# Power.net
KiCad netlist of a schematic drawn in Altium Designer
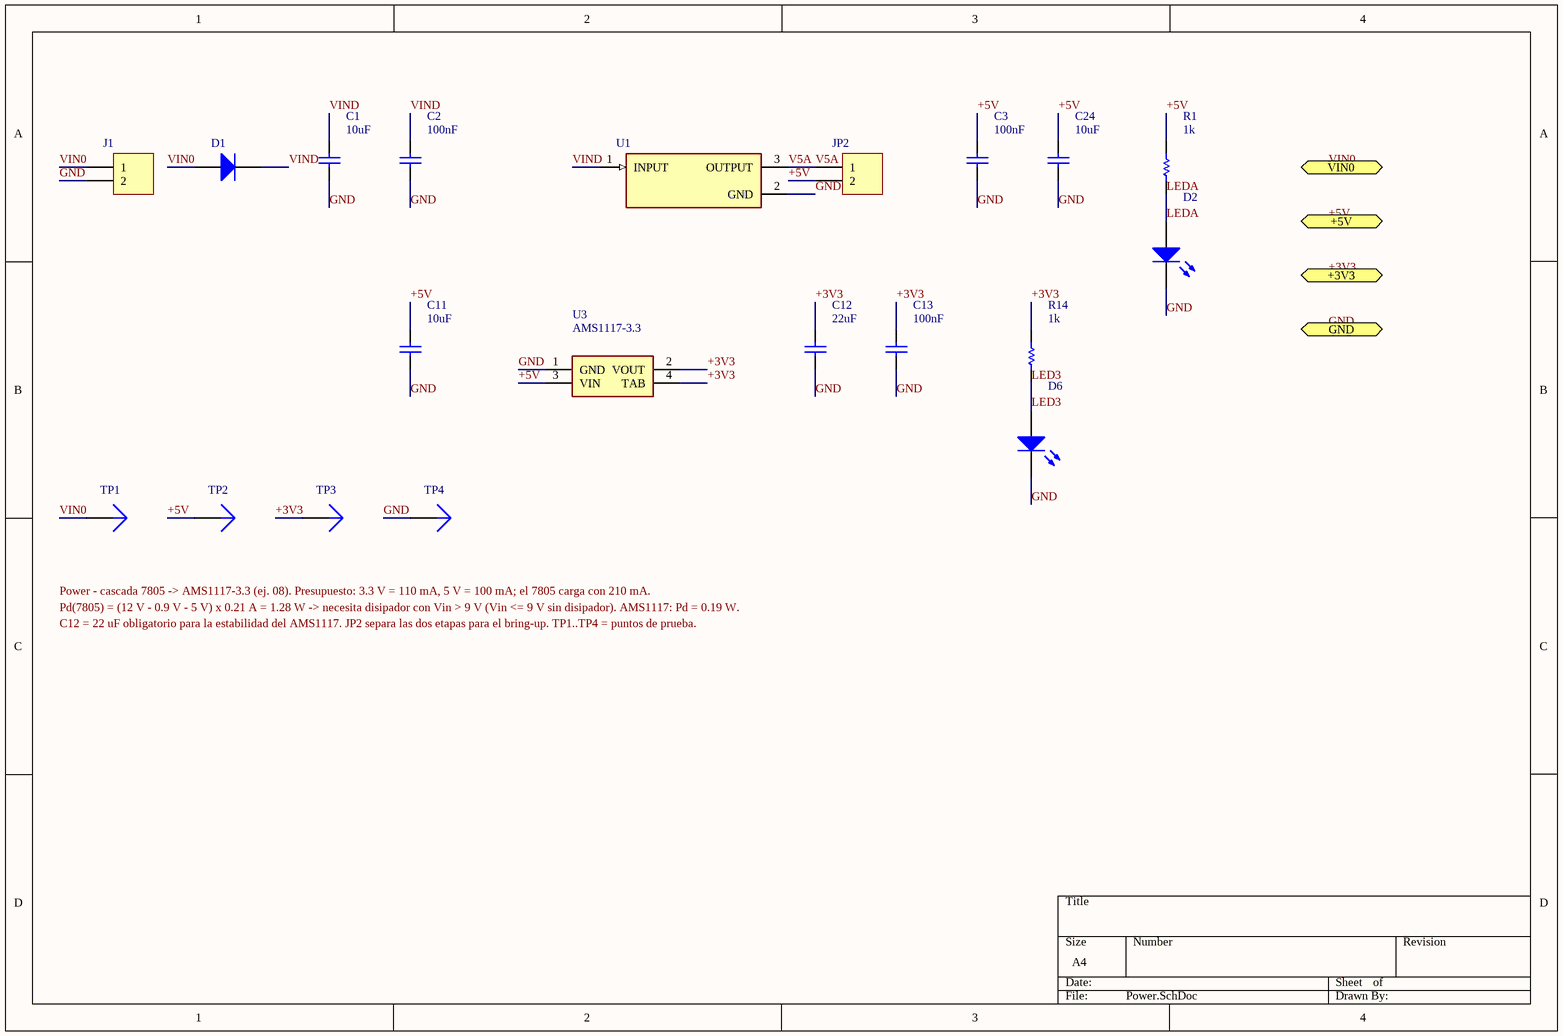
[diagram p0: Power.SchDoc]

(export (version "E")
  (design (tool "Eeschema 10.0.6"))
  (components
    (comp (ref "C1")
      (value "10uF")
      (description "Capacitor 10uF")
      (fields
        (field (name "MANUFACTURER") "KEMET")
        (field (name "MANUFACTURER PART NUMBER") "C0805C10610uF")
        (field (name "PUBLISHER") "Altium Limited")
      )
      (libsource (lib "Miscellaneous Devices") (part "Cap"))
    )
    (comp (ref "C2")
      (value "100nF")
      (description "Capacitor 100nF")
      (fields
        (field (name "MANUFACTURER") "KEMET")
        (field (name "MANUFACTURER PART NUMBER") "C0603C100nF")
        (field (name "PUBLISHER") "Altium Limited")
      )
      (libsource (lib "Miscellaneous Devices") (part "Cap"))
    )
    (comp (ref "C3")
      (value "100nF")
      (description "Capacitor 100nF")
      (fields
        (field (name "MANUFACTURER") "KEMET")
        (field (name "MANUFACTURER PART NUMBER") "C0603C100nF")
        (field (name "PUBLISHER") "Altium Limited")
      )
      (libsource (lib "Miscellaneous Devices") (part "Cap"))
    )
    (comp (ref "C11")
      (value "10uF")
      (description "Capacitor 10uF")
      (fields
        (field (name "MANUFACTURER") "KEMET")
        (field (name "MANUFACTURER PART NUMBER") "C0805C10610uF")
        (field (name "PUBLISHER") "Altium Limited")
      )
      (libsource (lib "Miscellaneous Devices") (part "Cap"))
    )
    (comp (ref "C12")
      (value "22uF")
      (description "Capacitor 22uF")
      (fields
        (field (name "MANUFACTURER") "KEMET")
        (field (name "MANUFACTURER PART NUMBER") "C1206C22622uF")
        (field (name "PUBLISHER") "Altium Limited")
      )
      (libsource (lib "Miscellaneous Devices") (part "Cap"))
    )
    (comp (ref "C13")
      (value "100nF")
      (description "Capacitor 100nF")
      (fields
        (field (name "MANUFACTURER") "KEMET")
        (field (name "MANUFACTURER PART NUMBER") "C0603C100nF")
        (field (name "PUBLISHER") "Altium Limited")
      )
      (libsource (lib "Miscellaneous Devices") (part "Cap"))
    )
    (comp (ref "C24")
      (value "10uF")
      (description "Capacitor 10uF")
      (fields
        (field (name "MANUFACTURER") "KEMET")
        (field (name "MANUFACTURER PART NUMBER") "C0805C10610uF")
        (field (name "PUBLISHER") "Altium Limited")
      )
      (libsource (lib "Miscellaneous Devices") (part "Cap"))
    )
    (comp (ref "D1")
      (value "Diode 1N4007")
      (description "Proteccion de polaridad inversa")
      (fields
        (field (name "MANUFACTURER") "Diodes Inc.")
        (field (name "MANUFACTURER PART NUMBER") "1N4007")
        (field (name "PUBLISHER") "Altium Limited")
      )
      (libsource (lib "Miscellaneous Devices") (part "Diode 1N4007"))
    )
    (comp (ref "D2")
      (value "LED1")
      (description "LED de alimentacion (5 V)")
      (fields
        (field (name "MANUFACTURER") "Kingbright")
        (field (name "MANUFACTURER PART NUMBER") "WP7113ID")
        (field (name "PUBLISHER") "Altium Limited")
      )
      (libsource (lib "Miscellaneous Devices") (part "LED1"))
    )
    (comp (ref "D6")
      (value "LED1")
      (description "LED de alimentacion (3.3 V)")
      (fields
        (field (name "MANUFACTURER") "Kingbright")
        (field (name "MANUFACTURER PART NUMBER") "WP7113GD")
        (field (name "PUBLISHER") "Altium Limited")
      )
      (libsource (lib "Miscellaneous Devices") (part "LED1"))
    )
    (comp (ref "J1")
      (value "Header 2")
      (description "Entrada 9-12 V DC: pin1 VIN, pin2 GND")
      (fields
        (field (name "MANUFACTURER") "Generic")
        (field (name "MANUFACTURER PART NUMBER") "Pin header 1x2 / borne")
        (field (name "PUBLISHER") "Altium Limited")
      )
      (libsource (lib "Miscellaneous Connectors") (part "Header 2"))
    )
    (comp (ref "JP2")
      (value "Header 2")
      (description "Jumper de separacion entre etapas")
      (fields
        (field (name "MANUFACTURER") "Generic")
        (field (name "MANUFACTURER PART NUMBER") "Pin header 1x2")
        (field (name "PUBLISHER") "Altium Limited")
      )
      (libsource (lib "Miscellaneous Connectors") (part "Header 2"))
    )
    (comp (ref "R1")
      (value "1k")
      (description "Resistor 1k 0603")
      (fields
        (field (name "MANUFACTURER") "Yageo")
        (field (name "MANUFACTURER PART NUMBER") "RC0603FR-071K")
        (field (name "PUBLISHER") "Altium Limited")
      )
      (libsource (lib "Miscellaneous Devices") (part "Res1"))
    )
    (comp (ref "R14")
      (value "1k")
      (description "Resistor 1k 0603")
      (fields
        (field (name "MANUFACTURER") "Yageo")
        (field (name "MANUFACTURER PART NUMBER") "RC0603FR-071K")
        (field (name "PUBLISHER") "Altium Limited")
      )
      (libsource (lib "Miscellaneous Devices") (part "Res1"))
    )
    (comp (ref "TP1")
      (value "Plug")
      (description "Punto de prueba VIN0")
      (fields
        (field (name "MANUFACTURER") "Generic")
        (field (name "MANUFACTURER PART NUMBER") "Test point")
        (field (name "PUBLISHER") "Altium Limited")
      )
      (libsource (lib "Miscellaneous Connectors") (part "Plug"))
    )
    (comp (ref "TP2")
      (value "Plug")
      (description "Punto de prueba +5V")
      (fields
        (field (name "MANUFACTURER") "Generic")
        (field (name "MANUFACTURER PART NUMBER") "Test point")
        (field (name "PUBLISHER") "Altium Limited")
      )
      (libsource (lib "Miscellaneous Connectors") (part "Plug"))
    )
    (comp (ref "TP3")
      (value "Plug")
      (description "Punto de prueba +3V3")
      (fields
        (field (name "MANUFACTURER") "Generic")
        (field (name "MANUFACTURER PART NUMBER") "Test point")
        (field (name "PUBLISHER") "Altium Limited")
      )
      (libsource (lib "Miscellaneous Connectors") (part "Plug"))
    )
    (comp (ref "TP4")
      (value "Plug")
      (description "Punto de prueba GND")
      (fields
        (field (name "MANUFACTURER") "Generic")
        (field (name "MANUFACTURER PART NUMBER") "Test point")
        (field (name "PUBLISHER") "Altium Limited")
      )
      (libsource (lib "Miscellaneous Connectors") (part "Plug"))
    )
    (comp (ref "U1")
      (value "LM7805T")
      (footprint "TO254P1011X457X1950-3")
      (description "Regulador 5 V, 1.5 A, TO-220 (necesita disipador si Vin>9 V)")
      (fields (field (name "MF") "TAEJIN") (field (name "MANUFACTURER") "STMicroelectronics"))
      (libsource (lib "LM7805T") (part "LM7805T"))
    )
    (comp (ref "U3")
      (value "AMS1117-3.3")
      (footprint "SOT223_N")
      (description "LDO 3.3 V 1 A SOT-223")
      (fields (field (name "MANUFACTURER") "Advanced Monolithic Systems"))
      (libsource (lib "*") (part "AMS1117-3.3"))
    )
  )
  (nets
    (net (code "1") (name "/+3V3") (class "Default")
      (node (ref "C12") (pin "2") (pinfunction "2_2") (pintype "passive"))
      (node (ref "C13") (pin "2") (pinfunction "2_2") (pintype "passive"))
      (node (ref "R14") (pin "2") (pinfunction "2_2") (pintype "passive"))
      (node (ref "TP3") (pin "1") (pinfunction "1_1") (pintype "passive"))
      (node (ref "U3") (pin "2") (pinfunction "VOUT_2") (pintype "power_in"))
      (node (ref "U3") (pin "4") (pinfunction "TAB_4") (pintype "power_in"))
    )
    (net (code "2") (name "/+5V") (class "Default")
      (node (ref "C11") (pin "2") (pinfunction "2_2") (pintype "passive"))
      (node (ref "C24") (pin "2") (pinfunction "2_2") (pintype "passive"))
      (node (ref "C3") (pin "2") (pinfunction "2_2") (pintype "passive"))
      (node (ref "JP2") (pin "2") (pinfunction "2_2") (pintype "passive"))
      (node (ref "R1") (pin "2") (pinfunction "2_2") (pintype "passive"))
      (node (ref "TP2") (pin "1") (pinfunction "1_1") (pintype "passive"))
      (node (ref "U3") (pin "3") (pinfunction "VIN_3") (pintype "power_in"))
    )
    (net (code "3") (name "/GND") (class "Default")
      (node (ref "C1") (pin "1") (pinfunction "1_1") (pintype "passive"))
      (node (ref "C11") (pin "1") (pinfunction "1_1") (pintype "passive"))
      (node (ref "C12") (pin "1") (pinfunction "1_1") (pintype "passive"))
      (node (ref "C13") (pin "1") (pinfunction "1_1") (pintype "passive"))
      (node (ref "C2") (pin "1") (pinfunction "1_1") (pintype "passive"))
      (node (ref "C24") (pin "1") (pinfunction "1_1") (pintype "passive"))
      (node (ref "C3") (pin "1") (pinfunction "1_1") (pintype "passive"))
      (node (ref "D2") (pin "2") (pinfunction "K_2") (pintype "passive"))
      (node (ref "D6") (pin "2") (pinfunction "K_2") (pintype "passive"))
      (node (ref "J1") (pin "2") (pinfunction "2_2") (pintype "passive"))
      (node (ref "TP4") (pin "1") (pinfunction "1_1") (pintype "passive"))
      (node (ref "U1") (pin "2") (pinfunction "GND_2") (pintype "power_in"))
      (node (ref "U3") (pin "1") (pinfunction "GND_1") (pintype "power_in"))
    )
    (net (code "4") (name "/LED3") (class "Default")
      (node (ref "D6") (pin "1") (pinfunction "A_1") (pintype "passive"))
      (node (ref "R14") (pin "1") (pinfunction "1_1") (pintype "passive"))
    )
    (net (code "5") (name "/LEDA") (class "Default")
      (node (ref "D2") (pin "1") (pinfunction "A_1") (pintype "passive"))
      (node (ref "R1") (pin "1") (pinfunction "1_1") (pintype "passive"))
    )
    (net (code "6") (name "/V5A") (class "Default")
      (node (ref "JP2") (pin "1") (pinfunction "1_1") (pintype "passive"))
      (node (ref "U1") (pin "3") (pinfunction "OUTPUT_3") (pintype "power_in"))
    )
    (net (code "7") (name "/VIN0") (class "Default")
      (node (ref "D1") (pin "1") (pinfunction "A_1") (pintype "passive"))
      (node (ref "J1") (pin "1") (pinfunction "1_1") (pintype "passive"))
      (node (ref "TP1") (pin "1") (pinfunction "1_1") (pintype "passive"))
    )
    (net (code "8") (name "/VIND") (class "Default")
      (node (ref "C1") (pin "2") (pinfunction "2_2") (pintype "passive"))
      (node (ref "C2") (pin "2") (pinfunction "2_2") (pintype "passive"))
      (node (ref "D1") (pin "2") (pinfunction "K_2") (pintype "passive"))
      (node (ref "U1") (pin "1") (pinfunction "INPUT_1") (pintype "input"))
    )
  )
)
